# microcontroller.net
KiCad netlist of a schematic drawn in Altium Designer
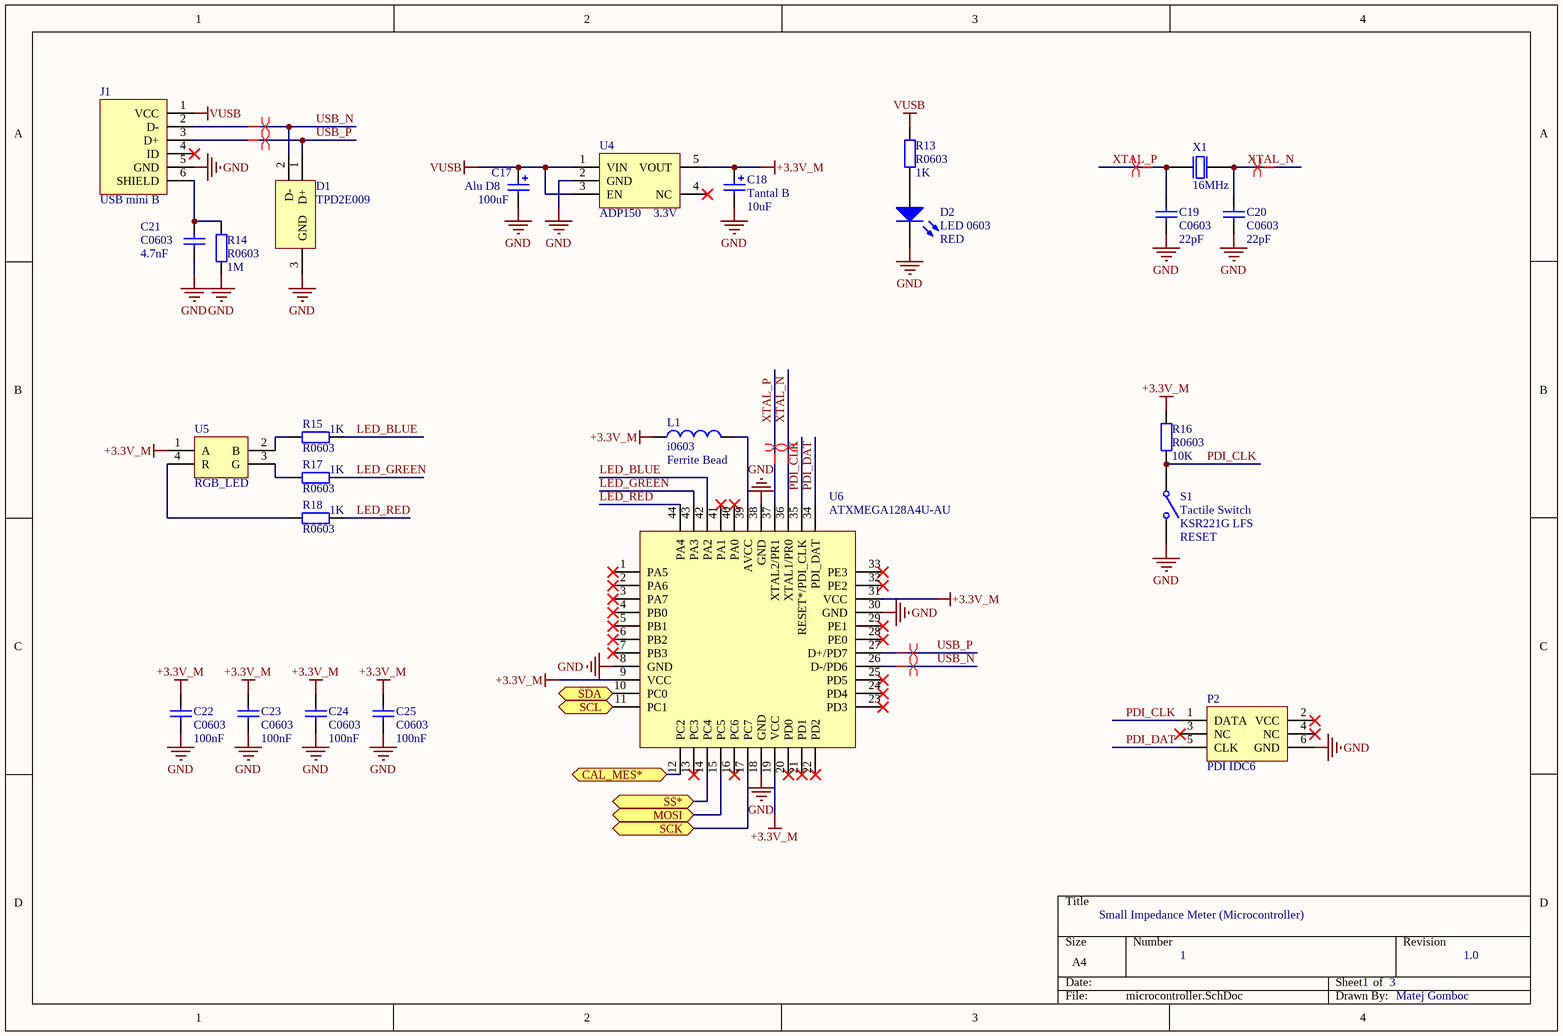
[diagram p0: microcontroller.SchDoc]

(export (version "E")
  (design (tool "Eeschema 10.0.6"))
  (components
    (comp (ref "C17")
      (value "Alu D8")
      (footprint "PANASONIC SIZE D8")
      (description "Aluminium Electrolythic Capacitor")
      (fields (field (name "ALTIUM_VALUE") "100uF"))
      (libsource (lib "LSP_Schlib") (part "Capacitor Aluminium"))
    )
    (comp (ref "C18")
      (value "Tantal B")
      (footprint "AVX-CAPC3528_V")
      (description "Tantalum Capacitor")
      (fields (field (name "ALTIUM_VALUE") "10uF"))
      (libsource (lib "LSP_Schlib") (part "Capacitor Tantalum"))
    )
    (comp (ref "C19")
      (value "C0603")
      (footprint "0603_HandSoldering")
      (description "Ceramic Capacitor")
      (fields (field (name "ALTIUM_VALUE") "22pF"))
      (libsource (lib "LSP_Schlib") (part "Capacitor"))
    )
    (comp (ref "C20")
      (value "C0603")
      (footprint "0603_HandSoldering")
      (description "Ceramic Capacitor")
      (fields (field (name "ALTIUM_VALUE") "22pF"))
      (libsource (lib "LSP_Schlib") (part "Capacitor"))
    )
    (comp (ref "C21")
      (value "C0603")
      (footprint "0603_HandSoldering")
      (description "Ceramic Capacitor")
      (fields (field (name "ALTIUM_VALUE") "4.7nF"))
      (libsource (lib "LSP_Schlib") (part "Capacitor"))
    )
    (comp (ref "C22")
      (value "C0603")
      (footprint "0603_HandSoldering")
      (description "Ceramic Capacitor")
      (fields (field (name "ALTIUM_VALUE") "100nF"))
      (libsource (lib "LSP_Schlib") (part "Capacitor"))
    )
    (comp (ref "C23")
      (value "C0603")
      (footprint "0603_HandSoldering")
      (description "Ceramic Capacitor")
      (fields (field (name "ALTIUM_VALUE") "100nF"))
      (libsource (lib "LSP_Schlib") (part "Capacitor"))
    )
    (comp (ref "C24")
      (value "C0603")
      (footprint "0603_HandSoldering")
      (description "Ceramic Capacitor")
      (fields (field (name "ALTIUM_VALUE") "100nF"))
      (libsource (lib "LSP_Schlib") (part "Capacitor"))
    )
    (comp (ref "C25")
      (value "C0603")
      (footprint "0603_HandSoldering")
      (description "Ceramic Capacitor")
      (fields (field (name "ALTIUM_VALUE") "100nF"))
      (libsource (lib "LSP_Schlib") (part "Capacitor"))
    )
    (comp (ref "D1")
      (value "TPD2E009")
      (footprint "TPD2E009_SOT23_3")
      (description "ESD protection")
      (libsource (lib "LSP_Schlib") (part "TPD2E009"))
    )
    (comp (ref "D2")
      (value "LED 0603")
      (footprint "0603_LED")
      (description "SMD LED 0603")
      (fields (field (name "ALTIUM_VALUE") "RED"))
      (libsource (lib "LSP_Schlib") (part "LED"))
    )
    (comp (ref "J1")
      (value "USB mini B")
      (footprint "USB mini B receptacle")
      (description "USB 2.0 mini B receptacle")
      (libsource (lib "LSP_Schlib") (part "USB_mini_B"))
    )
    (comp (ref "L1")
      (value "i0603")
      (footprint "0603_HandSoldering")
      (description "Inductor")
      (fields (field (name "ALTIUM_VALUE") "Ferrite Bead"))
      (libsource (lib "LSP_Schlib") (part "Inductor"))
    )
    (comp (ref "P2")
      (value "PDI IDC6")
      (footprint "PDI_HDR2X3")
      (description "PDI Programming Interface")
      (libsource (lib "LSP_Schlib") (part "PDI_Header"))
    )
    (comp (ref "R13")
      (value "R0603")
      (footprint "0603_HandSoldering")
      (description "Resistor")
      (fields (field (name "ALTIUM_VALUE") "1K"))
      (libsource (lib "") (part "Resistor_3"))
    )
    (comp (ref "R14")
      (value "R0603")
      (footprint "0603_HandSoldering")
      (description "Resistor")
      (fields (field (name "ALTIUM_VALUE") "1M"))
      (libsource (lib "") (part "Resistor_2"))
    )
    (comp (ref "R15")
      (value "R0603")
      (footprint "0603_HandSoldering")
      (description "Resistor")
      (fields (field (name "ALTIUM_VALUE") "1K"))
      (libsource (lib "") (part "Resistor_1"))
    )
    (comp (ref "R16")
      (value "R0603")
      (footprint "0603_HandSoldering")
      (description "Resistor")
      (fields (field (name "ALTIUM_VALUE") "10K"))
      (libsource (lib "") (part "Resistor_2"))
    )
    (comp (ref "R17")
      (value "R0603")
      (footprint "0603_HandSoldering")
      (description "Resistor")
      (fields (field (name "ALTIUM_VALUE") "1K"))
      (libsource (lib "LSP_Schlib") (part "Resistor"))
    )
    (comp (ref "R18")
      (value "R0603")
      (footprint "0603_HandSoldering")
      (description "Resistor")
      (fields (field (name "ALTIUM_VALUE") "1K"))
      (libsource (lib "LSP_Schlib") (part "Resistor"))
    )
    (comp (ref "S1")
      (value "Tactile Switch")
      (footprint "KSR221G_LFS_Tactile_Switch")
      (description "KSR221G LFS Tactile Switch")
      (fields (field (name "ALTIUM_VALUE") "KSR221G LFS") (field (name "NOTE") "RESET"))
      (libsource (lib "LSP_Schlib") (part "SW-SPST"))
    )
    (comp (ref "U4")
      (value "ADP150")
      (footprint "ADP150")
      (description "100 mA Voltage Regulator")
      (fields (field (name "ALTIUM_VALUE") "3.3V"))
      (libsource (lib "LSP_Schlib") (part "ADP150"))
    )
    (comp (ref "U5")
      (value "RGB_LED")
      (footprint "PLCC-4_LED")
      (description "RGB LED ASMB-MTB0-0A3A2")
      (libsource (lib "LSP_Schlib") (part "RGB_LED"))
    )
    (comp (ref "U6")
      (value "ATXMEGA128A4U-AU")
      (footprint "ATXMEGAA4U_TQFP44")
      (description "8/16-bit Atmel XMEGA Microcontroller")
      (libsource (lib "LSP_Schlib") (part "ATXMEGA128A4U-AU"))
    )
    (comp (ref "X1")
      (value "16MHz")
      (footprint "XTAL_TH_LOW")
      (description "XTAL TH Low Profile")
      (libsource (lib "LSP_Schlib") (part "XTAL_TH_LOW"))
    )
  )
  (nets
    (net (code "1") (name "+3.3V_M") (class "Default")
      (node (ref "C18") (pin "1") (pinfunction "1_1") (pintype "passive"))
      (node (ref "C22") (pin "1") (pinfunction "1_1") (pintype "passive"))
      (node (ref "C23") (pin "1") (pinfunction "1_1") (pintype "passive"))
      (node (ref "C24") (pin "1") (pinfunction "1_1") (pintype "passive"))
      (node (ref "C25") (pin "1") (pinfunction "1_1") (pintype "passive"))
      (node (ref "L1") (pin "1") (pinfunction "1_1") (pintype "passive"))
      (node (ref "R16") (pin "2") (pinfunction "2_2") (pintype "passive"))
      (node (ref "U4") (pin "5") (pinfunction "VOUT_5") (pintype "passive"))
      (node (ref "U5") (pin "1") (pinfunction "A_1") (pintype "passive"))
      (node (ref "U6") (pin "19") (pinfunction "VCC_19") (pintype "passive"))
      (node (ref "U6") (pin "31") (pinfunction "VCC_31") (pintype "passive"))
      (node (ref "U6") (pin "9") (pinfunction "VCC_9") (pintype "passive"))
    )
    (net (code "2") (name "/CAL_MES*") (class "Default")
      (node (ref "U6") (pin "12") (pinfunction "PC2_12") (pintype "passive"))
    )
    (net (code "3") (name "/LED_BLUE") (class "Default")
      (node (ref "R15") (pin "2") (pinfunction "2_2") (pintype "passive"))
      (node (ref "U6") (pin "42") (pinfunction "PA2_42") (pintype "passive"))
    )
    (net (code "4") (name "/LED_GREEN") (class "Default")
      (node (ref "R17") (pin "1") (pinfunction "1_1") (pintype "passive"))
      (node (ref "U6") (pin "43") (pinfunction "PA3_43") (pintype "passive"))
    )
    (net (code "5") (name "/LED_RED") (class "Default")
      (node (ref "R18") (pin "1") (pinfunction "1_1") (pintype "passive"))
      (node (ref "U6") (pin "44") (pinfunction "PA4_44") (pintype "passive"))
    )
    (net (code "6") (name "/MOSI") (class "Default")
      (node (ref "U6") (pin "15") (pinfunction "PC5_15") (pintype "passive"))
    )
    (net (code "7") (name "/PDI_CLK") (class "Default")
      (node (ref "P2") (pin "1") (pinfunction "DATA_1") (pintype "passive"))
      (node (ref "R16") (pin "1") (pinfunction "1_1") (pintype "passive"))
      (node (ref "S1") (pin "1") (pinfunction "COMMON_1") (pintype "passive"))
      (node (ref "U6") (pin "35") (pinfunction "RESET*/PDI_CLK_35") (pintype "passive"))
    )
    (net (code "8") (name "/PDI_DAT") (class "Default")
      (node (ref "P2") (pin "5") (pinfunction "CLK_5") (pintype "passive"))
      (node (ref "U6") (pin "34") (pinfunction "PDI_DAT_34") (pintype "passive"))
    )
    (net (code "9") (name "/SCK") (class "Default")
      (node (ref "U6") (pin "17") (pinfunction "PC7_17") (pintype "passive"))
    )
    (net (code "10") (name "/SCL") (class "Default")
      (node (ref "U6") (pin "11") (pinfunction "PC1_11") (pintype "passive"))
    )
    (net (code "11") (name "/SDA") (class "Default")
      (node (ref "U6") (pin "10") (pinfunction "PC0_10") (pintype "passive"))
    )
    (net (code "12") (name "/SS*") (class "Default")
      (node (ref "U6") (pin "14") (pinfunction "PC4_14") (pintype "passive"))
    )
    (net (code "13") (name "/USB_N") (class "Default")
      (node (ref "D1") (pin "2") (pinfunction "D-_2") (pintype "passive"))
      (node (ref "J1") (pin "2") (pinfunction "D-_2") (pintype "passive"))
      (node (ref "U6") (pin "26") (pinfunction "D-/PD6_26") (pintype "passive"))
    )
    (net (code "14") (name "/USB_P") (class "Default")
      (node (ref "D1") (pin "1") (pinfunction "D+_1") (pintype "passive"))
      (node (ref "J1") (pin "3") (pinfunction "D+_3") (pintype "passive"))
      (node (ref "U6") (pin "27") (pinfunction "D+/PD7_27") (pintype "passive"))
    )
    (net (code "15") (name "/XTAL_N") (class "Default")
      (node (ref "C20") (pin "2") (pinfunction "2_2") (pintype "passive"))
      (node (ref "U6") (pin "36") (pinfunction "XTAL1/PR0_36") (pintype "passive"))
      (node (ref "X1") (pin "2") (pinfunction "out_2") (pintype "passive"))
    )
    (net (code "16") (name "/XTAL_P") (class "Default")
      (node (ref "C19") (pin "2") (pinfunction "2_2") (pintype "passive"))
      (node (ref "U6") (pin "37") (pinfunction "XTAL2/PR1_37") (pintype "passive"))
      (node (ref "X1") (pin "1") (pinfunction "inp_1") (pintype "passive"))
    )
    (net (code "17") (name "GND") (class "Default")
      (node (ref "C17") (pin "2") (pinfunction "2_2") (pintype "passive"))
      (node (ref "C18") (pin "2") (pinfunction "2_2") (pintype "passive"))
      (node (ref "C19") (pin "1") (pinfunction "1_1") (pintype "passive"))
      (node (ref "C20") (pin "1") (pinfunction "1_1") (pintype "passive"))
      (node (ref "C21") (pin "1") (pinfunction "1_1") (pintype "passive"))
      (node (ref "C22") (pin "2") (pinfunction "2_2") (pintype "passive"))
      (node (ref "C23") (pin "2") (pinfunction "2_2") (pintype "passive"))
      (node (ref "C24") (pin "2") (pinfunction "2_2") (pintype "passive"))
      (node (ref "C25") (pin "2") (pinfunction "2_2") (pintype "passive"))
      (node (ref "D1") (pin "3") (pinfunction "GND_3") (pintype "passive"))
      (node (ref "D2") (pin "2") (pinfunction "K_2") (pintype "passive"))
      (node (ref "J1") (pin "5") (pinfunction "GND_5") (pintype "passive"))
      (node (ref "P2") (pin "6") (pinfunction "GND_6") (pintype "passive"))
      (node (ref "R14") (pin "1") (pinfunction "1_1") (pintype "passive"))
      (node (ref "S1") (pin "2") (pinfunction "NO_2") (pintype "passive"))
      (node (ref "U4") (pin "2") (pinfunction "GND_2") (pintype "passive"))
      (node (ref "U6") (pin "18") (pinfunction "GND_18") (pintype "passive"))
      (node (ref "U6") (pin "30") (pinfunction "GND_30") (pintype "passive"))
      (node (ref "U6") (pin "38") (pinfunction "GND_38") (pintype "passive"))
      (node (ref "U6") (pin "8") (pinfunction "GND_8") (pintype "passive"))
    )
    (net (code "18") (name "Net-(D2-A)") (class "Default")
      (node (ref "D2") (pin "1") (pinfunction "A_1") (pintype "passive"))
      (node (ref "R13") (pin "2") (pinfunction "2_2") (pintype "passive"))
    )
    (net (code "19") (name "Net-(J1-SHIELD)") (class "Default")
      (node (ref "C21") (pin "2") (pinfunction "2_2") (pintype "passive"))
      (node (ref "J1") (pin "6") (pinfunction "SHIELD_6") (pintype "passive"))
      (node (ref "R14") (pin "2") (pinfunction "2_2") (pintype "passive"))
    )
    (net (code "20") (name "Net-(U5-B)") (class "Default")
      (node (ref "R15") (pin "1") (pinfunction "1_1") (pintype "passive"))
      (node (ref "U5") (pin "2") (pinfunction "B_2") (pintype "passive"))
    )
    (net (code "21") (name "Net-(U5-G)") (class "Default")
      (node (ref "R17") (pin "2") (pinfunction "2_2") (pintype "passive"))
      (node (ref "U5") (pin "3") (pinfunction "G_3") (pintype "passive"))
    )
    (net (code "22") (name "Net-(U5-R)") (class "Default")
      (node (ref "R18") (pin "2") (pinfunction "2_2") (pintype "passive"))
      (node (ref "U5") (pin "4") (pinfunction "R_4") (pintype "passive"))
    )
    (net (code "23") (name "Net-(U6-AVCC)") (class "Default")
      (node (ref "L1") (pin "2") (pinfunction "2_2") (pintype "passive"))
      (node (ref "U6") (pin "39") (pinfunction "AVCC_39") (pintype "passive"))
    )
    (net (code "24") (name "VUSB") (class "Default")
      (node (ref "C17") (pin "1") (pinfunction "1_1") (pintype "passive"))
      (node (ref "J1") (pin "1") (pinfunction "VCC_1") (pintype "passive"))
      (node (ref "R13") (pin "1") (pinfunction "1_1") (pintype "passive"))
      (node (ref "U4") (pin "1") (pinfunction "VIN_1") (pintype "passive"))
      (node (ref "U4") (pin "3") (pinfunction "EN_3") (pintype "passive"))
    )
    (net (code "25") (name "unconnected-(J1-ID-Pad4)") (class "Default")
      (node (ref "J1") (pin "4") (pinfunction "ID_4") (pintype "passive+no_connect"))
    )
    (net (code "26") (name "unconnected-(P2-NC-Pad3)") (class "Default")
      (node (ref "P2") (pin "3") (pinfunction "NC_3") (pintype "passive+no_connect"))
    )
    (net (code "27") (name "unconnected-(P2-NC-Pad4)") (class "Default")
      (node (ref "P2") (pin "4") (pinfunction "NC_4") (pintype "passive+no_connect"))
    )
    (net (code "28") (name "unconnected-(P2-VCC-Pad2)") (class "Default")
      (node (ref "P2") (pin "2") (pinfunction "VCC_2") (pintype "passive+no_connect"))
    )
    (net (code "29") (name "unconnected-(U4-NC-Pad4)") (class "Default")
      (node (ref "U4") (pin "4") (pinfunction "NC_4") (pintype "passive+no_connect"))
    )
    (net (code "30") (name "unconnected-(U6-PA0-Pad40)") (class "Default")
      (node (ref "U6") (pin "40") (pinfunction "PA0_40") (pintype "passive+no_connect"))
    )
    (net (code "31") (name "unconnected-(U6-PA1-Pad41)") (class "Default")
      (node (ref "U6") (pin "41") (pinfunction "PA1_41") (pintype "passive+no_connect"))
    )
    (net (code "32") (name "unconnected-(U6-PA5-Pad1)") (class "Default")
      (node (ref "U6") (pin "1") (pinfunction "PA5_1") (pintype "passive+no_connect"))
    )
    (net (code "33") (name "unconnected-(U6-PA6-Pad2)") (class "Default")
      (node (ref "U6") (pin "2") (pinfunction "PA6_2") (pintype "passive+no_connect"))
    )
    (net (code "34") (name "unconnected-(U6-PA7-Pad3)") (class "Default")
      (node (ref "U6") (pin "3") (pinfunction "PA7_3") (pintype "passive+no_connect"))
    )
    (net (code "35") (name "unconnected-(U6-PB0-Pad4)") (class "Default")
      (node (ref "U6") (pin "4") (pinfunction "PB0_4") (pintype "passive+no_connect"))
    )
    (net (code "36") (name "unconnected-(U6-PB1-Pad5)") (class "Default")
      (node (ref "U6") (pin "5") (pinfunction "PB1_5") (pintype "passive+no_connect"))
    )
    (net (code "37") (name "unconnected-(U6-PB2-Pad6)") (class "Default")
      (node (ref "U6") (pin "6") (pinfunction "PB2_6") (pintype "passive+no_connect"))
    )
    (net (code "38") (name "unconnected-(U6-PB3-Pad7)") (class "Default")
      (node (ref "U6") (pin "7") (pinfunction "PB3_7") (pintype "passive+no_connect"))
    )
    (net (code "39") (name "unconnected-(U6-PC3-Pad13)") (class "Default")
      (node (ref "U6") (pin "13") (pinfunction "PC3_13") (pintype "passive+no_connect"))
    )
    (net (code "40") (name "unconnected-(U6-PC6-Pad16)") (class "Default")
      (node (ref "U6") (pin "16") (pinfunction "PC6_16") (pintype "passive+no_connect"))
    )
    (net (code "41") (name "unconnected-(U6-PD0-Pad20)") (class "Default")
      (node (ref "U6") (pin "20") (pinfunction "PD0_20") (pintype "passive+no_connect"))
    )
    (net (code "42") (name "unconnected-(U6-PD1-Pad21)") (class "Default")
      (node (ref "U6") (pin "21") (pinfunction "PD1_21") (pintype "passive+no_connect"))
    )
    (net (code "43") (name "unconnected-(U6-PD2-Pad22)") (class "Default")
      (node (ref "U6") (pin "22") (pinfunction "PD2_22") (pintype "passive+no_connect"))
    )
    (net (code "44") (name "unconnected-(U6-PD3-Pad23)") (class "Default")
      (node (ref "U6") (pin "23") (pinfunction "PD3_23") (pintype "passive+no_connect"))
    )
    (net (code "45") (name "unconnected-(U6-PD4-Pad24)") (class "Default")
      (node (ref "U6") (pin "24") (pinfunction "PD4_24") (pintype "passive+no_connect"))
    )
    (net (code "46") (name "unconnected-(U6-PD5-Pad25)") (class "Default")
      (node (ref "U6") (pin "25") (pinfunction "PD5_25") (pintype "passive+no_connect"))
    )
    (net (code "47") (name "unconnected-(U6-PE0-Pad28)") (class "Default")
      (node (ref "U6") (pin "28") (pinfunction "PE0_28") (pintype "passive+no_connect"))
    )
    (net (code "48") (name "unconnected-(U6-PE1-Pad29)") (class "Default")
      (node (ref "U6") (pin "29") (pinfunction "PE1_29") (pintype "passive+no_connect"))
    )
    (net (code "49") (name "unconnected-(U6-PE2-Pad32)") (class "Default")
      (node (ref "U6") (pin "32") (pinfunction "PE2_32") (pintype "passive+no_connect"))
    )
    (net (code "50") (name "unconnected-(U6-PE3-Pad33)") (class "Default")
      (node (ref "U6") (pin "33") (pinfunction "PE3_33") (pintype "passive+no_connect"))
    )
  )
)
